# Controller.net
KiCad netlist of a schematic drawn in Altium Designer
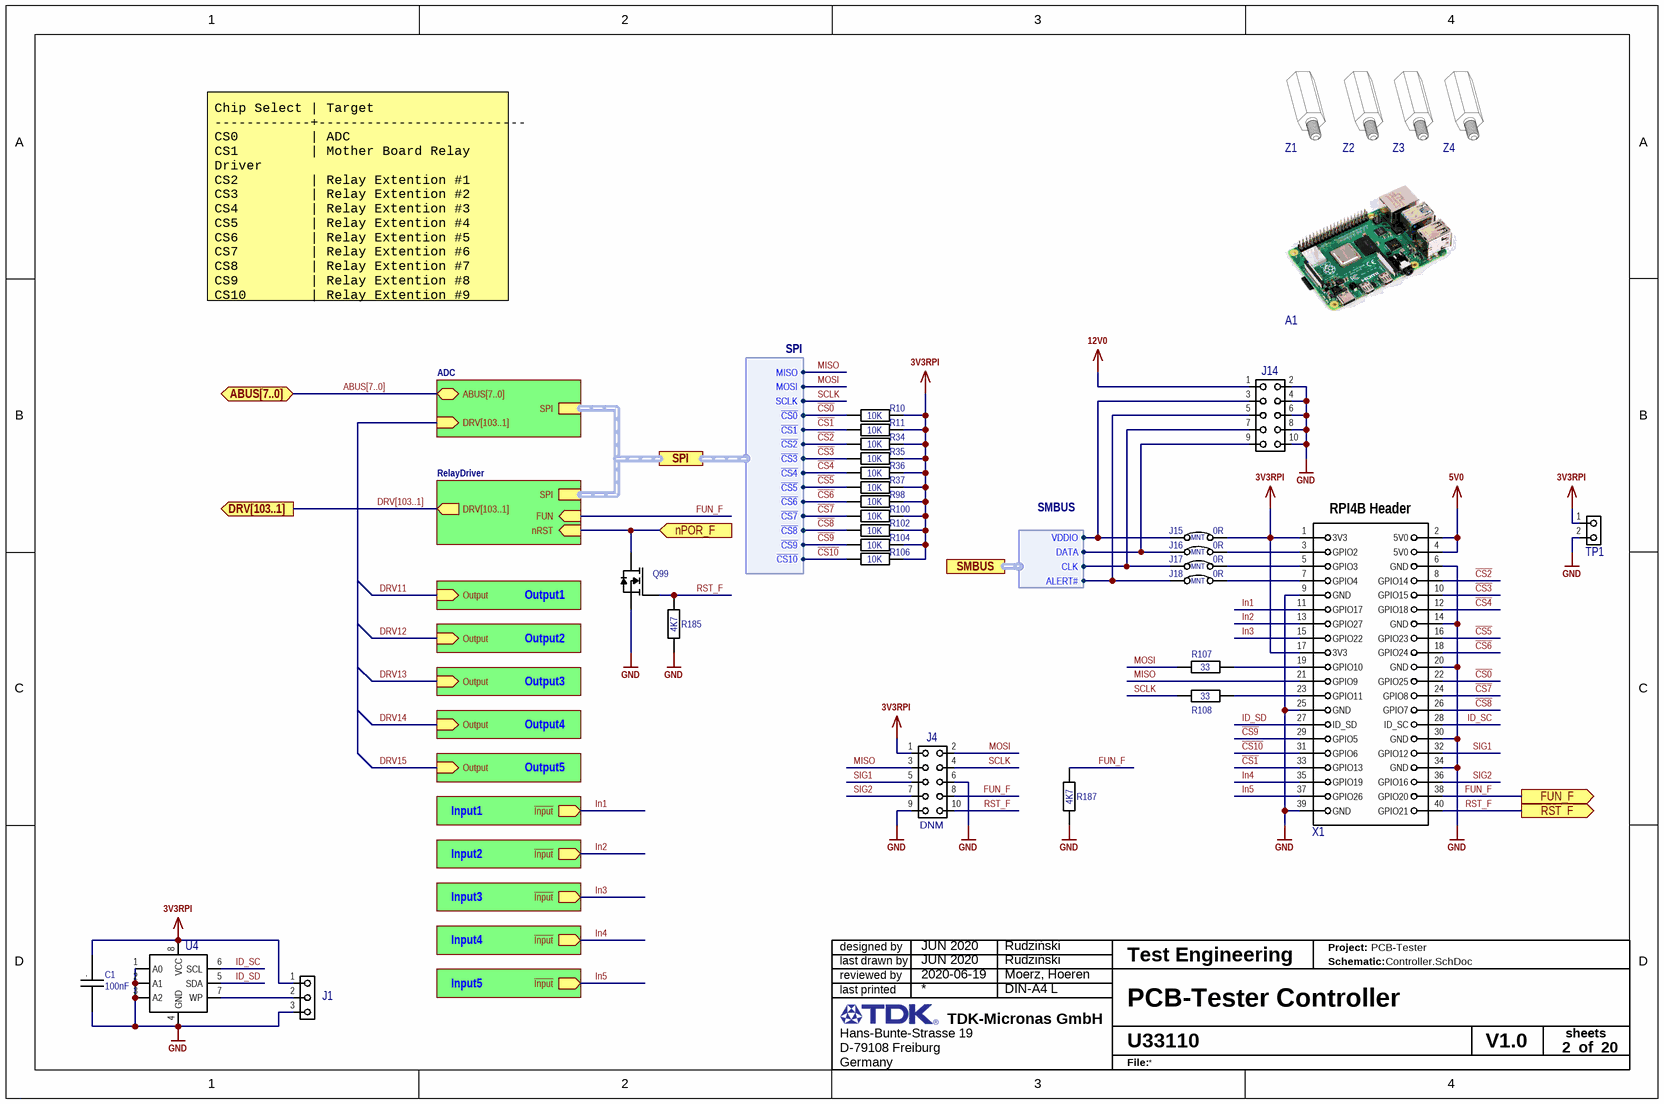
[diagram p0: Controller.SchDoc]

(export (version "E")
  (design (tool "Eeschema 10.0.6"))
  (components
    (comp (ref "A1")
      (value "A")
      (footprint "RPI4B")
      (description "RASPBERRY PI 4 MODEL B 4GB SDRAM")
      (fields
        (field (name "02. DISTRIBUTOR PART NUMBER") "1690-RASPBERRYPI4B/4GB-ND")
        (field (name "07. MANUFACTURER  PART NUMBER") "RASPBERRY PI 4B/4GB")
        (field (name "13. CREATED DATE/NAME") "??? / Hören")
      )
      (libsource (lib "PCB-Tester-Board-V1") (part "RPI4B"))
    )
    (comp (ref "C1")
      (value "100nF")
      (footprint "C0402 Reflow")
      (description "CAP CER 0.1UF 25V X7R 0402")
      (fields
        (field (name "TOLERANCE") "±20%")
        (field (name "02. DISTRIBUTOR PART NUMBER") "311-2077-6-ND")
        (field (name "13. CREATED DATE/NAME") "AUG2018/Hören")
      )
      (libsource (lib "chickenfood") (part "C"))
    )
    (comp (ref "J1")
      (value "J")
      (footprint "Header 100mil 3x1")
      (description "CONN HEADER VERT 3POS 2.54MM")
      (fields
        (field (name "02. DISTRIBUTOR PART NUMBER") "HMTSW-103-07-G-S-240")
        (field (name "13. CREATED DATE/NAME") "AUG2018/Hören")
      )
      (libsource (lib "chickenfood") (part "Header 3Pins 100mil"))
    )
    (comp (ref "J4")
      (value "J")
      (footprint "Header 100mil 5x2")
      (fields
        (field (name "02. DISTRIBUTOR PART NUMBER") "HMTSW-103-07-G-S-240")
        (field (name "NICNAME") "DNM")
        (field (name "13. CREATED DATE/NAME") "AUG2018/Hören")
      )
      (libsource (lib "PCB-Tester-Board-V1") (part "Header 5x2Pins 100mil"))
    )
    (comp (ref "J14")
      (value "J")
      (footprint "Header 100mil 5x2")
      (description ".100\" High-Temp Variable Post Height Terminal Strip")
      (fields
        (field (name "02. DISTRIBUTOR PART NUMBER") "HMTSW-105-07-G-D-240")
        (field (name "13. CREATED DATE/NAME") "AUG2018/Hören")
      )
      (libsource (lib "PCB-Tester-Board-V1") (part "Header 5x2Pins 100mil"))
    )
    (comp (ref "J15")
      (value "0R")
      (footprint "JumperSMD")
      (description "RES SMD 0 OHM JUMPER 1/10W 0603")
      (fields
        (field (name "02. DISTRIBUTOR PART NUMBER") "311-0.0GRDKR-ND")
        (field (name "07. MANUFACTURER  PART NUMBER") "RC0603JR-070RL")
        (field (name "POPULATED") "MNT")
      )
      (libsource (lib "chickenfood") (part "Jumper SMD"))
    )
    (comp (ref "J16")
      (value "0R")
      (footprint "JumperSMD")
      (description "RES SMD 0 OHM JUMPER 1/10W 0603")
      (fields
        (field (name "02. DISTRIBUTOR PART NUMBER") "311-0.0GRDKR-ND")
        (field (name "07. MANUFACTURER  PART NUMBER") "RC0603JR-070RL")
        (field (name "POPULATED") "MNT")
      )
      (libsource (lib "chickenfood") (part "Jumper SMD"))
    )
    (comp (ref "J17")
      (value "0R")
      (footprint "JumperSMD")
      (description "RES SMD 0 OHM JUMPER 1/10W 0603")
      (fields
        (field (name "02. DISTRIBUTOR PART NUMBER") "311-0.0GRDKR-ND")
        (field (name "07. MANUFACTURER  PART NUMBER") "RC0603JR-070RL")
        (field (name "POPULATED") "MNT")
      )
      (libsource (lib "chickenfood") (part "Jumper SMD"))
    )
    (comp (ref "J18")
      (value "0R")
      (footprint "JumperSMD")
      (description "RES SMD 0 OHM JUMPER 1/10W 0603")
      (fields
        (field (name "02. DISTRIBUTOR PART NUMBER") "311-0.0GRDKR-ND")
        (field (name "07. MANUFACTURER  PART NUMBER") "RC0603JR-070RL")
        (field (name "POPULATED") "MNT")
      )
      (libsource (lib "chickenfood") (part "Jumper SMD"))
    )
    (comp (ref "Q99")
      (value "Q")
      (footprint "SOT23-3")
      (description "MOSFET N-CH 25V 680MA SOT-23")
      (fields
        (field (name "02. DISTRIBUTOR PART NUMBER") "FDV303NDKR-ND")
        (field (name "07. MANUFACTURER  PART NUMBER") "FDV303N")
        (field (name "13. CREATED DATE/NAME") "AUG 2018 / Hören")
      )
      (libsource (lib "PCB-Tester-Board-V1") (part "FDV303N"))
    )
    (comp (ref "R10")
      (value "10K")
      (footprint "R0402 Reflow")
      (description "RES SMD 10K OHM 1% 1/16W 0402")
      (fields
        (field (name "TOLERANCE") "±1%")
        (field (name "02. DISTRIBUTOR PART NUMBER") "311-10.0KLRDKR-ND")
        (field (name "13. CREATED DATE/NAME") "AUG2018/Hören")
      )
      (libsource (lib "PCB-Tester-Board-V1") (part "R_10"))
    )
    (comp (ref "R11")
      (value "10K")
      (footprint "R0402 Reflow")
      (description "RES SMD 10K OHM 1% 1/16W 0402")
      (fields
        (field (name "TOLERANCE") "±1%")
        (field (name "02. DISTRIBUTOR PART NUMBER") "311-10.0KLRDKR-ND")
        (field (name "13. CREATED DATE/NAME") "AUG2018/Hören")
      )
      (libsource (lib "PCB-Tester-Board-V1") (part "R_10"))
    )
    (comp (ref "R34")
      (value "10K")
      (footprint "R0402 Reflow")
      (description "RES SMD 10K OHM 1% 1/16W 0402")
      (fields
        (field (name "TOLERANCE") "±1%")
        (field (name "02. DISTRIBUTOR PART NUMBER") "311-10.0KLRDKR-ND")
        (field (name "13. CREATED DATE/NAME") "AUG2018/Hören")
      )
      (libsource (lib "PCB-Tester-Board-V1") (part "R_10"))
    )
    (comp (ref "R35")
      (value "10K")
      (footprint "R0402 Reflow")
      (description "RES SMD 10K OHM 1% 1/16W 0402")
      (fields
        (field (name "TOLERANCE") "±1%")
        (field (name "02. DISTRIBUTOR PART NUMBER") "311-10.0KLRDKR-ND")
        (field (name "13. CREATED DATE/NAME") "AUG2018/Hören")
      )
      (libsource (lib "PCB-Tester-Board-V1") (part "R_10"))
    )
    (comp (ref "R36")
      (value "10K")
      (footprint "R0402 Reflow")
      (description "RES SMD 10K OHM 1% 1/16W 0402")
      (fields
        (field (name "TOLERANCE") "±1%")
        (field (name "02. DISTRIBUTOR PART NUMBER") "311-10.0KLRDKR-ND")
        (field (name "13. CREATED DATE/NAME") "AUG2018/Hören")
      )
      (libsource (lib "PCB-Tester-Board-V1") (part "R_10"))
    )
    (comp (ref "R37")
      (value "10K")
      (footprint "R0402 Reflow")
      (description "RES SMD 10K OHM 1% 1/16W 0402")
      (fields
        (field (name "TOLERANCE") "±1%")
        (field (name "02. DISTRIBUTOR PART NUMBER") "311-10.0KLRDKR-ND")
        (field (name "13. CREATED DATE/NAME") "AUG2018/Hören")
      )
      (libsource (lib "PCB-Tester-Board-V1") (part "R_10"))
    )
    (comp (ref "R98")
      (value "10K")
      (footprint "R0402 Reflow")
      (description "RES SMD 10K OHM 1% 1/16W 0402")
      (fields
        (field (name "TOLERANCE") "±1%")
        (field (name "02. DISTRIBUTOR PART NUMBER") "311-10.0KLRDKR-ND")
        (field (name "13. CREATED DATE/NAME") "AUG2018/Hören")
      )
      (libsource (lib "PCB-Tester-Board-V1") (part "R_10"))
    )
    (comp (ref "R100")
      (value "10K")
      (footprint "R0402 Reflow")
      (description "RES SMD 10K OHM 1% 1/16W 0402")
      (fields
        (field (name "TOLERANCE") "±1%")
        (field (name "02. DISTRIBUTOR PART NUMBER") "311-10.0KLRDKR-ND")
        (field (name "13. CREATED DATE/NAME") "AUG2018/Hören")
      )
      (libsource (lib "PCB-Tester-Board-V1") (part "R_10"))
    )
    (comp (ref "R102")
      (value "10K")
      (footprint "R0402 Reflow")
      (description "RES SMD 10K OHM 1% 1/16W 0402")
      (fields
        (field (name "TOLERANCE") "±1%")
        (field (name "02. DISTRIBUTOR PART NUMBER") "311-10.0KLRDKR-ND")
        (field (name "13. CREATED DATE/NAME") "AUG2018/Hören")
      )
      (libsource (lib "PCB-Tester-Board-V1") (part "R_10"))
    )
    (comp (ref "R104")
      (value "10K")
      (footprint "R0402 Reflow")
      (description "RES SMD 10K OHM 1% 1/16W 0402")
      (fields
        (field (name "TOLERANCE") "±1%")
        (field (name "02. DISTRIBUTOR PART NUMBER") "311-10.0KLRDKR-ND")
        (field (name "13. CREATED DATE/NAME") "AUG2018/Hören")
      )
      (libsource (lib "PCB-Tester-Board-V1") (part "R_10"))
    )
    (comp (ref "R106")
      (value "10K")
      (footprint "R0402 Reflow")
      (description "RES SMD 10K OHM 1% 1/16W 0402")
      (fields
        (field (name "TOLERANCE") "±1%")
        (field (name "02. DISTRIBUTOR PART NUMBER") "311-10.0KLRDKR-ND")
        (field (name "13. CREATED DATE/NAME") "AUG2018/Hören")
      )
      (libsource (lib "PCB-Tester-Board-V1") (part "R_10"))
    )
    (comp (ref "R107")
      (value "33")
      (footprint "R0402 Reflow")
      (description "RES SMD 33 OHM 1% 1/16W 0402")
      (fields
        (field (name "TOLERANCE") "±1%")
        (field (name "02. DISTRIBUTOR PART NUMBER") "311-33.0LRDKR-ND")
        (field (name "13. CREATED DATE/NAME") "AUG2018/Hören")
      )
      (libsource (lib "PCB-Tester-Board-V1") (part "R_19"))
    )
    (comp (ref "R108")
      (value "33")
      (footprint "R0402 Reflow")
      (description "RES SMD 33 OHM 1% 1/16W 0402")
      (fields
        (field (name "TOLERANCE") "±1%")
        (field (name "02. DISTRIBUTOR PART NUMBER") "311-33.0LRDKR-ND")
        (field (name "13. CREATED DATE/NAME") "AUG2018/Hören")
      )
      (libsource (lib "PCB-Tester-Board-V1") (part "R_19"))
    )
    (comp (ref "R185")
      (value "4K7")
      (footprint "R0603 Reflow")
      (description "RES SMD 4.7K OHM 1% 1/10W 0603")
      (fields
        (field (name "TOLERANCE") "±1%")
        (field (name "02. DISTRIBUTOR PART NUMBER") "311-4.70KHRCT-ND")
        (field (name "13. CREATED DATE/NAME") "AUG2018/Hören")
      )
      (libsource (lib "chickenfood") (part "R"))
    )
    (comp (ref "R187")
      (value "4K7")
      (footprint "R0603 Reflow")
      (description "RES SMD 4.7K OHM 1% 1/10W 0603")
      (fields
        (field (name "TOLERANCE") "±1%")
        (field (name "02. DISTRIBUTOR PART NUMBER") "311-4.70KHRCT-ND")
        (field (name "13. CREATED DATE/NAME") "AUG2018/Hören")
      )
      (libsource (lib "chickenfood") (part "R"))
    )
    (comp (ref "TP1")
      (value "TP")
      (footprint "DualTestpoint 100mils")
      (description "Dual testpoint, pitch 2.54mm")
      (fields
        (field (name "02. DISTRIBUTOR PART NUMBER") "HMTSW-103-07-G-S-240")
        (field (name "13. CREATED DATE/NAME") "AUG2018/Hören")
      )
      (libsource (lib "PCB-Tester-Board-V1") (part "DualTestpoint 100mils"))
    )
    (comp (ref "U4")
      (value "U")
      (footprint "SOIC8 (R-8)")
      (description "IC EEPROM 256K I2C 400KHZ 8SOIC")
      (fields
        (field (name "02. DISTRIBUTOR PART NUMBER") "24LC256T-I/SNDKR-ND")
        (field (name "07. MANUFACTURER  PART NUMBER") "24LC256T-I/SN")
        (field (name "13. CREATED DATE/NAME") "AUG 2018 / Hören")
      )
      (libsource (lib "tom") (part "24LC256T-I/SN"))
    )
    (comp (ref "X1")
      (value "X")
      (footprint "RPI4B Footprint")
      (description "40 Position Elevated Socket Connector  Through Hole")
      (fields
        (field (name "02. DISTRIBUTOR PART NUMBER") "ESW-120-23-L-D-LL")
        (field (name "13. CREATED DATE/NAME") "??? / Hören")
      )
      (libsource (lib "Connectors") (part "RPI4B Footprint"))
    )
    (comp (ref "Z1")
      (value "Z")
      (footprint "HSM2.5-6.4-16-2")
      (description "HEX STANDOFF M2.5 BRASS 16MM")
      (fields
        (field (name "02. DISTRIBUTOR PART NUMBER") "HSM2.5-6.4-16-2-ND")
        (field (name "07. MANUFACTURER  PART NUMBER") "HSM2.5-6.4-16-2")
        (field (name "13. CREATED DATE/NAME") "??? / Hören")
      )
      (libsource (lib "PCB-Tester-Board-V1") (part "HSM2.5-6.4-16-2"))
    )
    (comp (ref "Z2")
      (value "Z")
      (footprint "HSM2.5-6.4-16-2")
      (description "HEX STANDOFF M2.5 BRASS 16MM")
      (fields
        (field (name "02. DISTRIBUTOR PART NUMBER") "HSM2.5-6.4-16-2-ND")
        (field (name "07. MANUFACTURER  PART NUMBER") "HSM2.5-6.4-16-2")
        (field (name "13. CREATED DATE/NAME") "??? / Hören")
      )
      (libsource (lib "PCB-Tester-Board-V1") (part "HSM2.5-6.4-16-2"))
    )
    (comp (ref "Z3")
      (value "Z")
      (footprint "HSM2.5-6.4-16-2")
      (description "HEX STANDOFF M2.5 BRASS 16MM")
      (fields
        (field (name "02. DISTRIBUTOR PART NUMBER") "HSM2.5-6.4-16-2-ND")
        (field (name "07. MANUFACTURER  PART NUMBER") "HSM2.5-6.4-16-2")
        (field (name "13. CREATED DATE/NAME") "??? / Hören")
      )
      (libsource (lib "PCB-Tester-Board-V1") (part "HSM2.5-6.4-16-2"))
    )
    (comp (ref "Z4")
      (value "Z")
      (footprint "HSM2.5-6.4-16-2")
      (description "HEX STANDOFF M2.5 BRASS 16MM")
      (fields
        (field (name "02. DISTRIBUTOR PART NUMBER") "HSM2.5-6.4-16-2-ND")
        (field (name "07. MANUFACTURER  PART NUMBER") "HSM2.5-6.4-16-2")
        (field (name "13. CREATED DATE/NAME") "??? / Hören")
      )
      (libsource (lib "PCB-Tester-Board-V1") (part "HSM2.5-6.4-16-2"))
    )
  )
  (nets
    (net (code "110") (name "/CS0") (class "Default")
      (node (ref "R10") (pin "1") (pinfunction "1_1") (pintype "passive"))
      (node (ref "X1") (pin "22") (pinfunction "GPIO25_22") (pintype "passive"))
    )
    (net (code "111") (name "/CS1") (class "Default")
      (node (ref "R11") (pin "1") (pinfunction "1_1") (pintype "passive"))
      (node (ref "X1") (pin "33") (pinfunction "GPIO13_33") (pintype "passive"))
    )
    (net (code "112") (name "/CS2") (class "Default")
      (node (ref "R34") (pin "1") (pinfunction "1_1") (pintype "passive"))
      (node (ref "X1") (pin "8") (pinfunction "GPIO14_8") (pintype "passive"))
    )
    (net (code "113") (name "/CS3") (class "Default")
      (node (ref "R35") (pin "1") (pinfunction "1_1") (pintype "passive"))
      (node (ref "X1") (pin "10") (pinfunction "GPIO15_10") (pintype "passive"))
    )
    (net (code "114") (name "/CS4") (class "Default")
      (node (ref "R36") (pin "1") (pinfunction "1_1") (pintype "passive"))
      (node (ref "X1") (pin "12") (pinfunction "GPIO18_12") (pintype "passive"))
    )
    (net (code "115") (name "/CS5") (class "Default")
      (node (ref "R37") (pin "1") (pinfunction "1_1") (pintype "passive"))
      (node (ref "X1") (pin "16") (pinfunction "GPIO23_16") (pintype "passive"))
    )
    (net (code "116") (name "/CS6") (class "Default")
      (node (ref "R98") (pin "1") (pinfunction "1_1") (pintype "passive"))
      (node (ref "X1") (pin "18") (pinfunction "GPIO24_18") (pintype "passive"))
    )
    (net (code "117") (name "/CS7") (class "Default")
      (node (ref "R100") (pin "1") (pinfunction "1_1") (pintype "passive"))
      (node (ref "X1") (pin "24") (pinfunction "GPIO8_24") (pintype "passive"))
    )
    (net (code "118") (name "/CS8") (class "Default")
      (node (ref "R102") (pin "1") (pinfunction "1_1") (pintype "passive"))
      (node (ref "X1") (pin "26") (pinfunction "GPIO7_26") (pintype "passive"))
    )
    (net (code "119") (name "/CS9") (class "Default")
      (node (ref "R104") (pin "1") (pinfunction "1_1") (pintype "passive"))
      (node (ref "X1") (pin "29") (pinfunction "GPIO5_29") (pintype "passive"))
    )
    (net (code "120") (name "/CS10") (class "Default")
      (node (ref "R106") (pin "1") (pinfunction "1_1") (pintype "passive"))
      (node (ref "X1") (pin "31") (pinfunction "GPIO6_31") (pintype "passive"))
    )
    (net (code "127") (name "/FUN_F") (class "Default")
      (node (ref "J4") (pin "8") (pinfunction "8_8") (pintype "passive"))
      (node (ref "R187") (pin "2") (pinfunction "2_2") (pintype "passive"))
      (node (ref "X1") (pin "38") (pinfunction "GPIO20_38") (pintype "passive"))
    )
    (net (code "128") (name "/ID_SC") (class "Default")
      (node (ref "U4") (pin "6") (pinfunction "SCL_6") (pintype "passive"))
      (node (ref "X1") (pin "28") (pinfunction "ID_SC_28") (pintype "passive"))
    )
    (net (code "129") (name "/ID_SD") (class "Default")
      (node (ref "U4") (pin "5") (pinfunction "SDA_5") (pintype "passive"))
      (node (ref "X1") (pin "27") (pinfunction "ID_SD_27") (pintype "passive"))
    )
    (net (code "130") (name "/In1") (class "Default")
      (node (ref "X1") (pin "11") (pinfunction "GPIO17_11") (pintype "passive"))
    )
    (net (code "131") (name "/In2") (class "Default")
      (node (ref "X1") (pin "13") (pinfunction "GPIO27_13") (pintype "passive"))
    )
    (net (code "132") (name "/In3") (class "Default")
      (node (ref "X1") (pin "15") (pinfunction "GPIO22_15") (pintype "passive"))
    )
    (net (code "133") (name "/In4") (class "Default")
      (node (ref "X1") (pin "35") (pinfunction "GPIO19_35") (pintype "passive"))
    )
    (net (code "134") (name "/In5") (class "Default")
      (node (ref "X1") (pin "37") (pinfunction "GPIO26_37") (pintype "passive"))
    )
    (net (code "135") (name "/MISO") (class "Default")
      (node (ref "J4") (pin "3") (pinfunction "3_3") (pintype "passive"))
      (node (ref "X1") (pin "21") (pinfunction "GPIO9_21") (pintype "passive"))
    )
    (net (code "136") (name "/MOSI") (class "Default")
      (node (ref "J4") (pin "2") (pinfunction "2_2") (pintype "passive"))
      (node (ref "R107") (pin "1") (pinfunction "1_1") (pintype "passive"))
    )
    (net (code "137") (name "/RST_F") (class "Default")
      (node (ref "J4") (pin "10") (pinfunction "10_10") (pintype "passive"))
      (node (ref "Q99") (pin "1") (pinfunction "G_1") (pintype "passive"))
      (node (ref "R185") (pin "2") (pinfunction "2_2") (pintype "passive"))
      (node (ref "X1") (pin "40") (pinfunction "GPIO21_40") (pintype "passive"))
    )
    (net (code "138") (name "/SCLK") (class "Default")
      (node (ref "J4") (pin "4") (pinfunction "4_4") (pintype "passive"))
      (node (ref "R108") (pin "1") (pinfunction "1_1") (pintype "passive"))
    )
    (net (code "139") (name "/SIG1") (class "Default")
      (node (ref "J4") (pin "5") (pinfunction "5_5") (pintype "passive"))
      (node (ref "X1") (pin "32") (pinfunction "GPIO12_32") (pintype "passive"))
    )
    (net (code "140") (name "/SIG2") (class "Default")
      (node (ref "J4") (pin "7") (pinfunction "7_7") (pintype "passive"))
      (node (ref "X1") (pin "36") (pinfunction "GPIO16_36") (pintype "passive"))
    )
    (net (code "141") (name "/nPOR_F") (class "Default")
      (node (ref "Q99") (pin "3") (pinfunction "D_3") (pintype "passive"))
    )
    (net (code "144") (name "3V3RPI") (class "Default")
      (node (ref "C1") (pin "1") (pinfunction "1_1") (pintype "passive"))
      (node (ref "J1") (pin "1") (pinfunction "1_1") (pintype "passive"))
      (node (ref "J15") (pin "2") (pinfunction "2_2") (pintype "passive"))
      (node (ref "J4") (pin "1") (pinfunction "1_1") (pintype "passive"))
      (node (ref "R10") (pin "2") (pinfunction "2_2") (pintype "passive"))
      (node (ref "R100") (pin "2") (pinfunction "2_2") (pintype "passive"))
      (node (ref "R102") (pin "2") (pinfunction "2_2") (pintype "passive"))
      (node (ref "R104") (pin "2") (pinfunction "2_2") (pintype "passive"))
      (node (ref "R106") (pin "2") (pinfunction "2_2") (pintype "passive"))
      (node (ref "R11") (pin "2") (pinfunction "2_2") (pintype "passive"))
      (node (ref "R34") (pin "2") (pinfunction "2_2") (pintype "passive"))
      (node (ref "R35") (pin "2") (pinfunction "2_2") (pintype "passive"))
      (node (ref "R36") (pin "2") (pinfunction "2_2") (pintype "passive"))
      (node (ref "R37") (pin "2") (pinfunction "2_2") (pintype "passive"))
      (node (ref "R98") (pin "2") (pinfunction "2_2") (pintype "passive"))
      (node (ref "TP1") (pin "1") (pinfunction "1_1") (pintype "passive"))
      (node (ref "U4") (pin "8") (pinfunction "VCC_8") (pintype "power_in"))
      (node (ref "X1") (pin "1") (pinfunction "3V3_1") (pintype "passive"))
      (node (ref "X1") (pin "17") (pinfunction "3V3_17") (pintype "passive"))
    )
    (net (code "145") (name "5V0") (class "Default")
      (node (ref "X1") (pin "2") (pinfunction "5V0_2") (pintype "passive"))
      (node (ref "X1") (pin "4") (pinfunction "5V0_4") (pintype "passive"))
    )
    (net (code "146") (name "12V0") (class "Default")
      (node (ref "J14") (pin "1") (pinfunction "1_1") (pintype "passive"))
    )
    (net (code "147") (name "GND") (class "Default")
      (node (ref "C1") (pin "2") (pinfunction "2_2") (pintype "passive"))
      (node (ref "J1") (pin "3") (pinfunction "3_3") (pintype "passive"))
      (node (ref "J14") (pin "10") (pinfunction "10_10") (pintype "passive"))
      (node (ref "J14") (pin "2") (pinfunction "2_2") (pintype "passive"))
      (node (ref "J14") (pin "4") (pinfunction "4_4") (pintype "passive"))
      (node (ref "J14") (pin "6") (pinfunction "6_6") (pintype "passive"))
      (node (ref "J14") (pin "8") (pinfunction "8_8") (pintype "passive"))
      (node (ref "J4") (pin "6") (pinfunction "6_6") (pintype "passive"))
      (node (ref "J4") (pin "9") (pinfunction "9_9") (pintype "passive"))
      (node (ref "Q99") (pin "2") (pinfunction "S_2") (pintype "passive"))
      (node (ref "R185") (pin "1") (pinfunction "1_1") (pintype "passive"))
      (node (ref "R187") (pin "1") (pinfunction "1_1") (pintype "passive"))
      (node (ref "TP1") (pin "2") (pinfunction "2_2") (pintype "passive"))
      (node (ref "U4") (pin "1") (pinfunction "A0_1") (pintype "passive"))
      (node (ref "U4") (pin "2") (pinfunction "A1_2") (pintype "passive"))
      (node (ref "U4") (pin "3") (pinfunction "A2_3") (pintype "passive"))
      (node (ref "U4") (pin "4") (pinfunction "GND_4") (pintype "power_in"))
      (node (ref "X1") (pin "14") (pinfunction "GND_14") (pintype "passive"))
      (node (ref "X1") (pin "20") (pinfunction "GND_20") (pintype "passive"))
      (node (ref "X1") (pin "25") (pinfunction "GND_25") (pintype "passive"))
      (node (ref "X1") (pin "30") (pinfunction "GND_30") (pintype "passive"))
      (node (ref "X1") (pin "34") (pinfunction "GND_34") (pintype "passive"))
      (node (ref "X1") (pin "39") (pinfunction "GND_39") (pintype "passive"))
      (node (ref "X1") (pin "6") (pinfunction "GND_6") (pintype "passive"))
      (node (ref "X1") (pin "9") (pinfunction "GND_9") (pintype "passive"))
    )
    (net (code "148") (name "Net-(J14-Pad3)") (class "Default")
      (node (ref "J14") (pin "3") (pinfunction "3_3") (pintype "passive"))
      (node (ref "J15") (pin "1") (pinfunction "1_1") (pintype "passive"))
    )
    (net (code "149") (name "Net-(J14-Pad5)") (class "Default")
      (node (ref "J14") (pin "5") (pinfunction "5_5") (pintype "passive"))
      (node (ref "J18") (pin "1") (pinfunction "1_1") (pintype "passive"))
    )
    (net (code "150") (name "Net-(J14-Pad7)") (class "Default")
      (node (ref "J14") (pin "7") (pinfunction "7_7") (pintype "passive"))
      (node (ref "J17") (pin "1") (pinfunction "1_1") (pintype "passive"))
    )
    (net (code "151") (name "Net-(J14-Pad9)") (class "Default")
      (node (ref "J14") (pin "9") (pinfunction "9_9") (pintype "passive"))
      (node (ref "J16") (pin "1") (pinfunction "1_1") (pintype "passive"))
    )
    (net (code "152") (name "Net-(U4-WP)") (class "Default")
      (node (ref "J1") (pin "2") (pinfunction "2_2") (pintype "passive"))
      (node (ref "U4") (pin "7") (pinfunction "WP_7") (pintype "passive"))
    )
    (net (code "153") (name "Net-(X1-GPIO2)") (class "Default")
      (node (ref "J16") (pin "2") (pinfunction "2_2") (pintype "passive"))
      (node (ref "X1") (pin "3") (pinfunction "GPIO2_3") (pintype "passive"))
    )
    (net (code "154") (name "Net-(X1-GPIO3)") (class "Default")
      (node (ref "J17") (pin "2") (pinfunction "2_2") (pintype "passive"))
      (node (ref "X1") (pin "5") (pinfunction "GPIO3_5") (pintype "passive"))
    )
    (net (code "155") (name "Net-(X1-GPIO4)") (class "Default")
      (node (ref "J18") (pin "2") (pinfunction "2_2") (pintype "passive"))
      (node (ref "X1") (pin "7") (pinfunction "GPIO4_7") (pintype "passive"))
    )
    (net (code "156") (name "Net-(X1-GPIO10)") (class "Default")
      (node (ref "R107") (pin "2") (pinfunction "2_2") (pintype "passive"))
      (node (ref "X1") (pin "19") (pinfunction "GPIO10_19") (pintype "passive"))
    )
    (net (code "157") (name "Net-(X1-GPIO11)") (class "Default")
      (node (ref "R108") (pin "2") (pinfunction "2_2") (pintype "passive"))
      (node (ref "X1") (pin "23") (pinfunction "GPIO11_23") (pintype "passive"))
    )
  )
)
